# 3-Power-Supply.net
KiCad netlist of a schematic drawn in Altium Designer
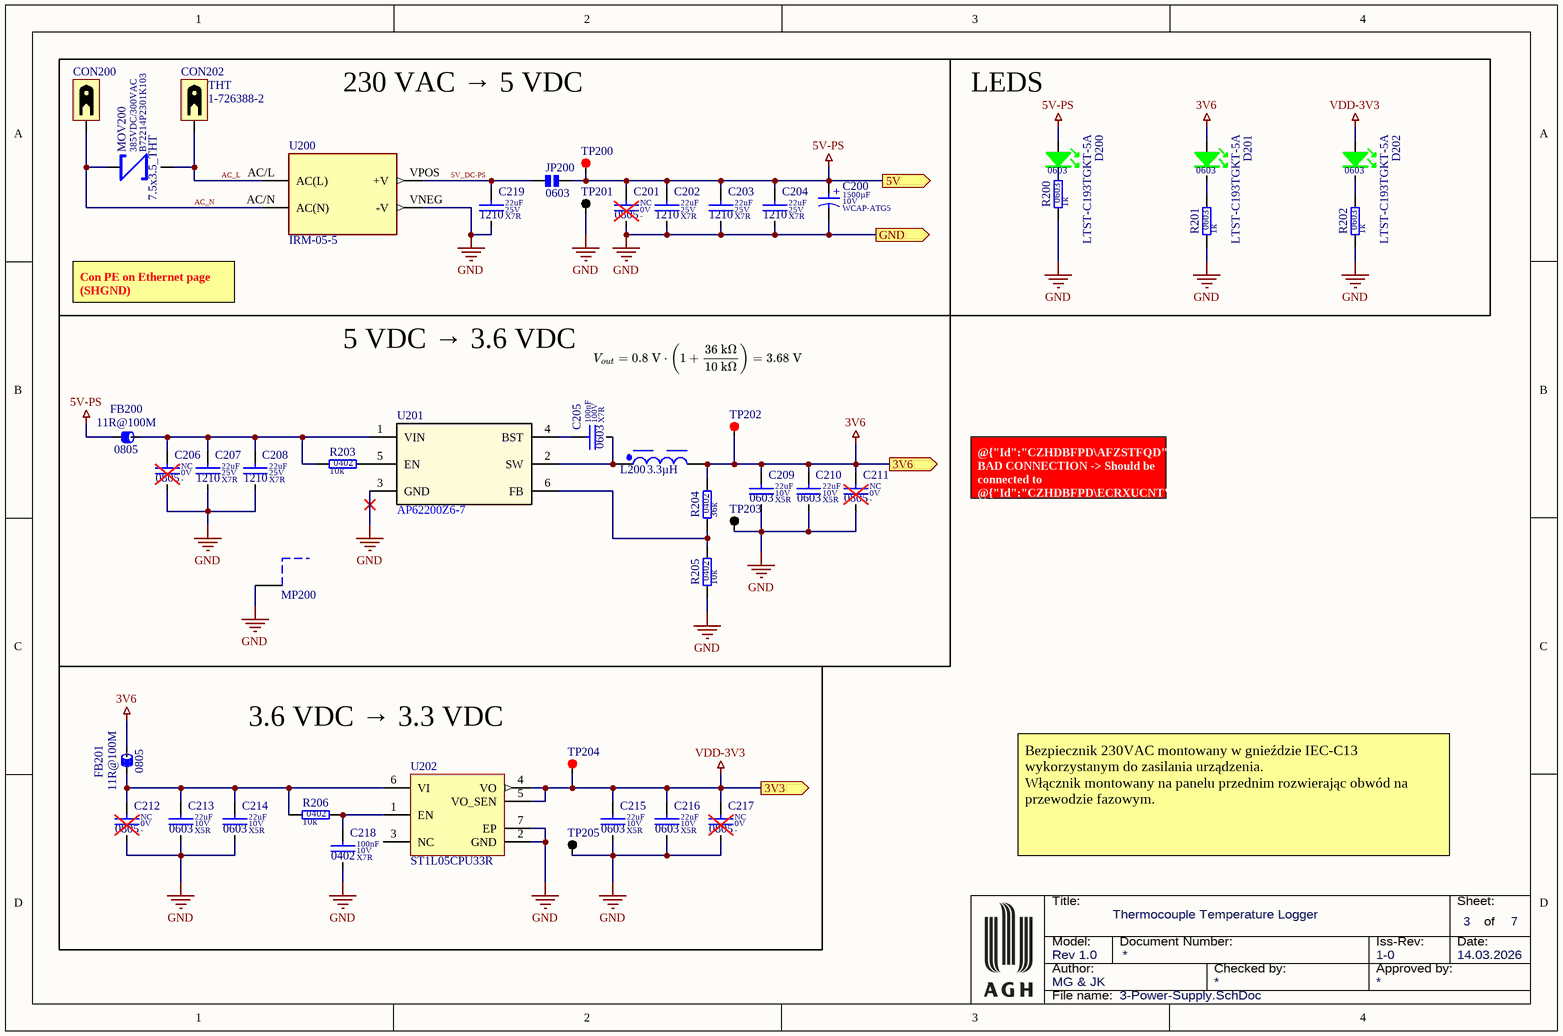
[diagram p0: 3-Power-Supply.SchDoc]

(export (version "E")
  (design (tool "Eeschema 10.0.6"))
  (components
    (comp (ref "C200")
      (value "1500µF")
      (footprint "WCAP-ATG5_D8H20")
      (description "WCAP-ATG5 Aluminum Electrolytic Capacitor, Radial, THT, D8 x H20mm, 1500µF, 10V")
      (fields
        (field (name "MANUFACTURER PART NUMBER") "860020274017")
        (field (name "MATCH CODE") "WCAP-ATG5")
        (field (name "MANUFACTURER") "Wurth Elektronik")
        (field (name "RATED VOLTAGE (DC)") "10V")
      )
      (libsource (lib "Altium_WCAP-ATG5 (rev22d)") (part "860020274017"))
    )
    (comp (ref "C201")
      (value "NC")
      (footprint "C_NC_0805_2012")
      (description "Capacitor")
      (fields
        (field (name "DIELECTRIC") "-")
        (field (name "VOLTAGE") "0V")
        (field (name "SCH_FOOTPRINT") "0805")
        (field (name "PART NUMBER") "C_GENERIC_0805")
      )
      (libsource (lib "Library") (part "C_NC"))
    )
    (comp (ref "C202")
      (value "22uF")
      (footprint "C_1210_3225")
      (description "Capacitor")
      (fields
        (field (name "DIELECTRIC") "X7R")
        (field (name "VOLTAGE") "25V")
        (field (name "SCH_FOOTPRINT") "1210")
        (field (name "PART NUMBER") "C_22uF_25V_X7R_1210_20")
        (field (name "MANUFACTURER") "Murata")
      )
      (libsource (lib "Library") (part "C"))
    )
    (comp (ref "C203")
      (value "22uF")
      (footprint "C_1210_3225")
      (description "Capacitor")
      (fields
        (field (name "DIELECTRIC") "X7R")
        (field (name "VOLTAGE") "25V")
        (field (name "SCH_FOOTPRINT") "1210")
        (field (name "PART NUMBER") "C_22uF_25V_X7R_1210_20")
        (field (name "MANUFACTURER") "Murata")
      )
      (libsource (lib "Library") (part "C"))
    )
    (comp (ref "C204")
      (value "22uF")
      (footprint "C_1210_3225")
      (description "Capacitor")
      (fields
        (field (name "DIELECTRIC") "X7R")
        (field (name "VOLTAGE") "25V")
        (field (name "SCH_FOOTPRINT") "1210")
        (field (name "PART NUMBER") "C_22uF_25V_X7R_1210_20")
        (field (name "MANUFACTURER") "Murata")
      )
      (libsource (lib "Library") (part "C"))
    )
    (comp (ref "C205")
      (value "100nF")
      (footprint "C_0603_1608")
      (description "Capacitor")
      (fields
        (field (name "DIELECTRIC") "X7R")
        (field (name "VOLTAGE") "100V")
        (field (name "SCH_FOOTPRINT") "0603")
        (field (name "PART NUMBER") "C_100nF_100V_X7R_0603_10")
        (field (name "MANUFACTURER") "Kemet")
      )
      (libsource (lib "Library") (part "C"))
    )
    (comp (ref "C206")
      (value "NC")
      (footprint "C_NC_0805_2012")
      (description "Capacitor")
      (fields
        (field (name "DIELECTRIC") "-")
        (field (name "VOLTAGE") "0V")
        (field (name "SCH_FOOTPRINT") "0805")
        (field (name "PART NUMBER") "C_GENERIC_0805")
      )
      (libsource (lib "Library") (part "C_NC"))
    )
    (comp (ref "C207")
      (value "22uF")
      (footprint "C_1210_3225")
      (description "Capacitor")
      (fields
        (field (name "DIELECTRIC") "X7R")
        (field (name "VOLTAGE") "25V")
        (field (name "SCH_FOOTPRINT") "1210")
        (field (name "PART NUMBER") "C_22uF_25V_X7R_1210_20")
        (field (name "MANUFACTURER") "Murata")
      )
      (libsource (lib "Library") (part "C"))
    )
    (comp (ref "C208")
      (value "22uF")
      (footprint "C_1210_3225")
      (description "Capacitor")
      (fields
        (field (name "DIELECTRIC") "X7R")
        (field (name "VOLTAGE") "25V")
        (field (name "SCH_FOOTPRINT") "1210")
        (field (name "PART NUMBER") "C_22uF_25V_X7R_1210_20")
        (field (name "MANUFACTURER") "Murata")
      )
      (libsource (lib "Library") (part "C"))
    )
    (comp (ref "C209")
      (value "22uF")
      (footprint "C_0603_1608")
      (description "Capacitor")
      (fields
        (field (name "DIELECTRIC") "X5R")
        (field (name "VOLTAGE") "10V")
        (field (name "SCH_FOOTPRINT") "0603")
        (field (name "PART NUMBER") "C_22uF_10V_X5R_0603_20")
        (field (name "MANUFACTURER") "Murata")
      )
      (libsource (lib "Library") (part "C"))
    )
    (comp (ref "C210")
      (value "22uF")
      (footprint "C_0603_1608")
      (description "Capacitor")
      (fields
        (field (name "DIELECTRIC") "X5R")
        (field (name "VOLTAGE") "10V")
        (field (name "SCH_FOOTPRINT") "0603")
        (field (name "PART NUMBER") "C_22uF_10V_X5R_0603_20")
        (field (name "MANUFACTURER") "Murata")
      )
      (libsource (lib "Library") (part "C"))
    )
    (comp (ref "C211")
      (value "NC")
      (footprint "C_NC_0805_2012")
      (description "Capacitor")
      (fields
        (field (name "DIELECTRIC") "-")
        (field (name "VOLTAGE") "0V")
        (field (name "SCH_FOOTPRINT") "0805")
        (field (name "PART NUMBER") "C_GENERIC_0805")
      )
      (libsource (lib "Library") (part "C_NC"))
    )
    (comp (ref "C212")
      (value "NC")
      (footprint "C_NC_0805_2012")
      (description "Capacitor")
      (fields
        (field (name "DIELECTRIC") "-")
        (field (name "VOLTAGE") "0V")
        (field (name "SCH_FOOTPRINT") "0805")
        (field (name "PART NUMBER") "C_GENERIC_0805")
      )
      (libsource (lib "Library") (part "C_NC"))
    )
    (comp (ref "C213")
      (value "22uF")
      (footprint "C_0603_1608")
      (description "Capacitor")
      (fields
        (field (name "DIELECTRIC") "X5R")
        (field (name "VOLTAGE") "10V")
        (field (name "SCH_FOOTPRINT") "0603")
        (field (name "PART NUMBER") "C_22uF_10V_X5R_0603_20")
        (field (name "MANUFACTURER") "Murata")
      )
      (libsource (lib "Library") (part "C"))
    )
    (comp (ref "C214")
      (value "22uF")
      (footprint "C_0603_1608")
      (description "Capacitor")
      (fields
        (field (name "DIELECTRIC") "X5R")
        (field (name "VOLTAGE") "10V")
        (field (name "SCH_FOOTPRINT") "0603")
        (field (name "PART NUMBER") "C_22uF_10V_X5R_0603_20")
        (field (name "MANUFACTURER") "Murata")
      )
      (libsource (lib "Library") (part "C"))
    )
    (comp (ref "C215")
      (value "22uF")
      (footprint "C_0603_1608")
      (description "Capacitor")
      (fields
        (field (name "DIELECTRIC") "X5R")
        (field (name "VOLTAGE") "10V")
        (field (name "SCH_FOOTPRINT") "0603")
        (field (name "PART NUMBER") "C_22uF_10V_X5R_0603_20")
        (field (name "MANUFACTURER") "Murata")
      )
      (libsource (lib "Library") (part "C"))
    )
    (comp (ref "C216")
      (value "22uF")
      (footprint "C_0603_1608")
      (description "Capacitor")
      (fields
        (field (name "DIELECTRIC") "X5R")
        (field (name "VOLTAGE") "10V")
        (field (name "SCH_FOOTPRINT") "0603")
        (field (name "PART NUMBER") "C_22uF_10V_X5R_0603_20")
        (field (name "MANUFACTURER") "Murata")
      )
      (libsource (lib "Library") (part "C"))
    )
    (comp (ref "C217")
      (value "NC")
      (footprint "C_NC_0805_2012")
      (description "Capacitor")
      (fields
        (field (name "DIELECTRIC") "-")
        (field (name "VOLTAGE") "0V")
        (field (name "SCH_FOOTPRINT") "0805")
        (field (name "PART NUMBER") "C_GENERIC_0805")
      )
      (libsource (lib "Library") (part "C_NC"))
    )
    (comp (ref "C218")
      (value "100nF")
      (footprint "C_0402_1005")
      (description "Capacitor")
      (fields
        (field (name "DIELECTRIC") "X7R")
        (field (name "VOLTAGE") "10V")
        (field (name "SCH_FOOTPRINT") "0402")
        (field (name "PART NUMBER") "C_100nF_10V_X7R_0402_10")
        (field (name "MANUFACTURER") "Murata")
      )
      (libsource (lib "Library") (part "C"))
    )
    (comp (ref "C219")
      (value "22uF")
      (footprint "C_1210_3225")
      (description "Capacitor")
      (fields
        (field (name "DIELECTRIC") "X7R")
        (field (name "VOLTAGE") "25V")
        (field (name "SCH_FOOTPRINT") "1210")
        (field (name "PART NUMBER") "C_22uF_25V_X7R_1210_20")
        (field (name "MANUFACTURER") "Murata")
      )
      (libsource (lib "Library") (part "C"))
    )
    (comp (ref "CON200")
      (value "Terminal for PE")
      (footprint "TP_1-726388-2")
      (description "Terminal")
      (fields
        (field (name "PART NUMBER") "TP_TERMINAL_1-726388-2")
        (field (name "MANUFACTURER") "TE Connectivity")
      )
      (libsource (lib "Library") (part "TP_TERMINAL"))
    )
    (comp (ref "CON202")
      (value "1-726388-2")
      (footprint "TP_1-726388-2")
      (description "Terminal")
      (fields
        (field (name "SCH_FOOTPRINT") "THT")
        (field (name "PART NUMBER") "TP_TERMINAL_1-726388-2")
        (field (name "MANUFACTURER") "TE Connectivity")
      )
      (libsource (lib "Library") (part "TP_TERMINAL"))
    )
    (comp (ref "D200")
      (value "LTST-C193TGKT-5A")
      (footprint "OL_0603_1608")
      (description "LED GREEN")
      (fields
        (field (name "SCH_FOOTPRINT") "0603")
        (field (name "PART NUMBER") "OL_G_0603_LTST-C193TGKT-5A")
        (field (name "MANUFACTURER") "Lite-On")
      )
      (libsource (lib "Library") (part "OL_G"))
    )
    (comp (ref "D201")
      (value "LTST-C193TGKT-5A")
      (footprint "OL_0603_1608")
      (description "LED GREEN")
      (fields
        (field (name "SCH_FOOTPRINT") "0603")
        (field (name "PART NUMBER") "OL_G_0603_LTST-C193TGKT-5A")
        (field (name "MANUFACTURER") "Lite-On")
      )
      (libsource (lib "Library") (part "OL_G"))
    )
    (comp (ref "D202")
      (value "LTST-C193TGKT-5A")
      (footprint "OL_0603_1608")
      (description "LED GREEN")
      (fields
        (field (name "SCH_FOOTPRINT") "0603")
        (field (name "PART NUMBER") "OL_G_0603_LTST-C193TGKT-5A")
        (field (name "MANUFACTURER") "Lite-On")
      )
      (libsource (lib "Library") (part "OL_G"))
    )
    (comp (ref "FB200")
      (value "11R@100M")
      (footprint "FB_0805_2012")
      (description "Ferrite Bead")
      (fields
        (field (name "SCH_FOOTPRINT") "0805")
        (field (name "PART NUMBER") "FB_2508051107Y0")
        (field (name "MANUFACTURER") "Fair-Rite")
      )
      (libsource (lib "Library") (part "FB"))
    )
    (comp (ref "FB201")
      (value "11R@100M")
      (footprint "FB_0805_2012")
      (description "Ferrite Bead")
      (fields
        (field (name "SCH_FOOTPRINT") "0805")
        (field (name "PART NUMBER") "FB_2508051107Y0")
        (field (name "MANUFACTURER") "Fair-Rite")
      )
      (libsource (lib "") (part "FB_1"))
    )
    (comp (ref "JP200")
      (value "Solder Jumper 0603/1608")
      (footprint "JP_0603_1608")
      (fields (field (name "SCH_FOOTPRINT") "0603") (field (name "PART NUMBER") "JP_0603_1608"))
      (libsource (lib "Library") (part "JP"))
    )
    (comp (ref "L200")
      (value "3.3µH, 2.1A")
      (footprint "WE-SPC_4828")
      (description "WE-SPC SMT Power Inductor, size 4828, 3.3µH, 2.1A, 0.057Ω")
      (fields
        (field (name "MANUFACTURER PART NUMBER") "74408942033")
        (field (name "MANUFACTURER") "Wurth Elektronik")
        (field (name "INDUCTANCE") "3.3µH")
      )
      (libsource (lib "WE-SPC (rev22d)") (part "74408942033"))
    )
    (comp (ref "MOV200")
      (value "B72214P2301K103")
      (footprint "MOV_AXIAL_7.5_3.5")
      (description "Varistor")
      (fields
        (field (name "SCH_FOOTPRINT") "7.5x3.5_THT")
        (field (name "VOLTAGE") "385VDC/300VAC")
        (field (name "PART NUMBER") "MOV_385VDC_300VAC_THT")
        (field (name "MANUFACTURER") "Epcos")
      )
      (libsource (lib "Library") (part "MOV"))
    )
    (comp (ref "MP200")
      (value "36702638")
      (footprint "36702638")
      (description "WE-SHC Shielding Cabinet, SMT Frame Seamless, Tin Plated, Tray, 26.3x19.8x8.1mm")
      (fields (field (name "MANUFACTURER") "Wurth Elektronik"))
      (libsource (lib "WE-SHC (rev24a)") (part "36702638"))
    )
    (comp (ref "R200")
      (value "1k")
      (footprint "R_0603_1608")
      (fields
        (field (name "SCH_FOOTPRINT") "0603")
        (field (name "PART NUMBER") "R_1k_0603_1_AECQ0")
        (field (name "VOLTAGE") "75V")
        (field (name "POWER") "100mW")
      )
      (libsource (lib "Library") (part "R"))
    )
    (comp (ref "R201")
      (value "1k")
      (footprint "R_0603_1608")
      (fields
        (field (name "SCH_FOOTPRINT") "0603")
        (field (name "PART NUMBER") "R_1k_0603_1_AECQ0")
        (field (name "VOLTAGE") "75V")
        (field (name "POWER") "100mW")
      )
      (libsource (lib "Library") (part "R"))
    )
    (comp (ref "R202")
      (value "1k")
      (footprint "R_0603_1608")
      (fields
        (field (name "SCH_FOOTPRINT") "0603")
        (field (name "PART NUMBER") "R_1k_0603_1_AECQ0")
        (field (name "VOLTAGE") "75V")
        (field (name "POWER") "100mW")
      )
      (libsource (lib "Library") (part "R"))
    )
    (comp (ref "R203")
      (value "10k")
      (footprint "R_0402_1005")
      (fields
        (field (name "SCH_FOOTPRINT") "0402")
        (field (name "PART NUMBER") "R_10k_0402_1")
        (field (name "VOLTAGE") "50V")
        (field (name "POWER") "63mW")
      )
      (libsource (lib "Library") (part "R"))
    )
    (comp (ref "R204")
      (value "36k")
      (footprint "R_0402_1005")
      (fields
        (field (name "SCH_FOOTPRINT") "0402")
        (field (name "PART NUMBER") "R_36k_0402_1_AECQ0")
        (field (name "VOLTAGE") "50V")
        (field (name "POWER") "100mW")
      )
      (libsource (lib "Library") (part "R"))
    )
    (comp (ref "R205")
      (value "10k")
      (footprint "R_0402_1005")
      (fields
        (field (name "SCH_FOOTPRINT") "0402")
        (field (name "PART NUMBER") "R_10k_0402_1")
        (field (name "VOLTAGE") "50V")
        (field (name "POWER") "63mW")
      )
      (libsource (lib "Library") (part "R"))
    )
    (comp (ref "R206")
      (value "10k")
      (footprint "R_0402_1005")
      (fields
        (field (name "SCH_FOOTPRINT") "0402")
        (field (name "PART NUMBER") "R_10k_0402_1")
        (field (name "VOLTAGE") "50V")
        (field (name "POWER") "63mW")
      )
      (libsource (lib "Library") (part "R"))
    )
    (comp (ref "TP200")
      (value "Test loop THT")
      (footprint "TP_KEYSTONE_5000_RED")
      (description "Testpoint")
      (fields (field (name "PART NUMBER") "TP_LOOP_MICRO_RED") (field (name "MANUFACTURER") "Keystone"))
      (libsource (lib "Library") (part "TP_TESTPOINT_RED"))
    )
    (comp (ref "TP201")
      (value "Test loop THT")
      (footprint "TP_KEYSTONE_5001_BLACK")
      (description "Testpoint")
      (fields (field (name "PART NUMBER") "TP_LOOP_MICRO_BLACK") (field (name "MANUFACTURER") "Keystone"))
      (libsource (lib "Library") (part "TP_TESTPOINT_BLACK"))
    )
    (comp (ref "TP202")
      (value "Test loop THT")
      (footprint "TP_KEYSTONE_5000_RED")
      (description "Testpoint")
      (fields (field (name "PART NUMBER") "TP_LOOP_MICRO_RED") (field (name "MANUFACTURER") "Keystone"))
      (libsource (lib "Library") (part "TP_TESTPOINT_RED"))
    )
    (comp (ref "TP203")
      (value "Test loop THT")
      (footprint "TP_KEYSTONE_5001_BLACK")
      (description "Testpoint")
      (fields (field (name "PART NUMBER") "TP_LOOP_MICRO_BLACK") (field (name "MANUFACTURER") "Keystone"))
      (libsource (lib "Library") (part "TP_TESTPOINT_BLACK"))
    )
    (comp (ref "TP204")
      (value "Test loop THT")
      (footprint "TP_KEYSTONE_5000_RED")
      (description "Testpoint")
      (fields (field (name "PART NUMBER") "TP_LOOP_MICRO_RED") (field (name "MANUFACTURER") "Keystone"))
      (libsource (lib "Library") (part "TP_TESTPOINT_RED"))
    )
    (comp (ref "TP205")
      (value "Test loop THT")
      (footprint "TP_KEYSTONE_5001_BLACK")
      (description "Testpoint")
      (fields (field (name "PART NUMBER") "TP_LOOP_MICRO_BLACK") (field (name "MANUFACTURER") "Keystone"))
      (libsource (lib "Library") (part "TP_TESTPOINT_BLACK"))
    )
    (comp (ref "U200")
      (value "IRM-05-5")
      (footprint "CONV_IRM-05-5")
      (description "Enclosed AC DC Converters 1 Uitgang 5V 1A 85 ~ 305 VAC, 120 ~ 430 VDC Input")
      (fields (field (name "MF") "MEAN WELL"))
      (libsource (lib "IRM-05-5") (part "IRM-05-5"))
    )
    (comp (ref "U201")
      (value "AP62200Z6-7")
      (footprint "SOT563-Z6_1_DIO")
      (description "Description")
      (fields (field (name "COPYRIGHT") "Copyright (C) 2025 Ultra Librarian. All rights reserved."))
      (libsource (lib "AP62200Z6-7") (part "AP62200Z6-7"))
    )
    (comp (ref "U202")
      (value "ST1L05CPU33R")
      (footprint "DFN6D_N")
      (description "Very Low Quiescent BiCMOS Voltage Regulator, 3.3V, 6-Pin VFDFPN, Tape and Reel")
      (libsource (lib "Altium Content Vault") (part "PM-REG-ST1L05C-SQ7"))
    )
  )
  (nets
    (net (code "1") (name "/5V_DC-PS") (class "Default")
      (node (ref "C219") (pin "1") (pinfunction "1_1") (pintype "passive"))
      (node (ref "JP200") (pin "1") (pinfunction "1_1") (pintype "passive"))
      (node (ref "U200") (pin "VPOS") (pinfunction "+V_VPOS") (pintype "output"))
    )
    (net (code "2") (name "/AC_L") (class "Default")
      (node (ref "CON202") (pin "1") (pinfunction "TP_1") (pintype "passive"))
      (node (ref "MOV200") (pin "1") (pintype "passive"))
      (node (ref "U200") (pin "AC/L") (pinfunction "AC(L)_AC/L") (pintype "passive"))
    )
    (net (code "3") (name "/AC_N") (class "Default")
      (node (ref "CON200") (pin "1") (pinfunction "TP_1") (pintype "passive"))
      (node (ref "MOV200") (pin "2") (pintype "passive"))
      (node (ref "U200") (pin "AC/N") (pinfunction "AC(N)_AC/N") (pintype "passive"))
    )
    (net (code "4") (name "3V6") (class "Default")
      (node (ref "C209") (pin "1") (pinfunction "1_1") (pintype "passive"))
      (node (ref "C210") (pin "1") (pinfunction "1_1") (pintype "passive"))
      (node (ref "C211") (pin "1") (pinfunction "1_1") (pintype "passive"))
      (node (ref "D201") (pin "2") (pinfunction "A_2") (pintype "passive"))
      (node (ref "FB201") (pin "2") (pintype "passive"))
      (node (ref "L200") (pin "2") (pinfunction "2_2") (pintype "passive"))
      (node (ref "R204") (pin "2") (pinfunction "2_2") (pintype "passive"))
      (node (ref "TP202") (pin "1") (pinfunction "TP_1") (pintype "passive"))
    )
    (net (code "5") (name "5V-PS") (class "Default")
      (node (ref "C200") (pin "1") (pinfunction "P_1") (pintype "passive"))
      (node (ref "C201") (pin "1") (pinfunction "1_1") (pintype "passive"))
      (node (ref "C202") (pin "1") (pinfunction "1_1") (pintype "passive"))
      (node (ref "C203") (pin "1") (pinfunction "1_1") (pintype "passive"))
      (node (ref "C204") (pin "1") (pinfunction "1_1") (pintype "passive"))
      (node (ref "D200") (pin "2") (pinfunction "A_2") (pintype "passive"))
      (node (ref "FB200") (pin "1") (pintype "passive"))
      (node (ref "JP200") (pin "2") (pinfunction "2_2") (pintype "passive"))
      (node (ref "TP200") (pin "1") (pinfunction "TP_1") (pintype "passive"))
    )
    (net (code "6") (name "GND") (class "Default")
      (node (ref "C200") (pin "2") (pinfunction "N_2") (pintype "passive"))
      (node (ref "C201") (pin "2") (pinfunction "2_2") (pintype "passive"))
      (node (ref "C202") (pin "2") (pinfunction "2_2") (pintype "passive"))
      (node (ref "C203") (pin "2") (pinfunction "2_2") (pintype "passive"))
      (node (ref "C204") (pin "2") (pinfunction "2_2") (pintype "passive"))
      (node (ref "C206") (pin "2") (pinfunction "2_2") (pintype "passive"))
      (node (ref "C207") (pin "2") (pinfunction "2_2") (pintype "passive"))
      (node (ref "C208") (pin "2") (pinfunction "2_2") (pintype "passive"))
      (node (ref "C209") (pin "2") (pinfunction "2_2") (pintype "passive"))
      (node (ref "C210") (pin "2") (pinfunction "2_2") (pintype "passive"))
      (node (ref "C211") (pin "2") (pinfunction "2_2") (pintype "passive"))
      (node (ref "C212") (pin "2") (pinfunction "2_2") (pintype "passive"))
      (node (ref "C213") (pin "2") (pinfunction "2_2") (pintype "passive"))
      (node (ref "C214") (pin "2") (pinfunction "2_2") (pintype "passive"))
      (node (ref "C215") (pin "2") (pinfunction "2_2") (pintype "passive"))
      (node (ref "C216") (pin "2") (pinfunction "2_2") (pintype "passive"))
      (node (ref "C217") (pin "2") (pinfunction "2_2") (pintype "passive"))
      (node (ref "C218") (pin "2") (pinfunction "2_2") (pintype "passive"))
      (node (ref "C219") (pin "2") (pinfunction "2_2") (pintype "passive"))
      (node (ref "MP200") (pin "1") (pinfunction "1_1") (pintype "passive"))
      (node (ref "R200") (pin "1") (pinfunction "1_1") (pintype "passive"))
      (node (ref "R201") (pin "1") (pinfunction "1_1") (pintype "passive"))
      (node (ref "R202") (pin "1") (pinfunction "1_1") (pintype "passive"))
      (node (ref "R205") (pin "1") (pinfunction "1_1") (pintype "passive"))
      (node (ref "TP201") (pin "1") (pinfunction "TP_1") (pintype "passive"))
      (node (ref "TP203") (pin "1") (pinfunction "TP_1") (pintype "passive"))
      (node (ref "TP205") (pin "1") (pinfunction "TP_1") (pintype "passive"))
      (node (ref "U200") (pin "VNEG") (pinfunction "-V_VNEG") (pintype "output"))
      (node (ref "U201") (pin "3") (pinfunction "GND_3") (pintype "passive"))
      (node (ref "U202") (pin "2") (pinfunction "GND_2") (pintype "passive"))
      (node (ref "U202") (pin "7") (pinfunction "EP_7") (pintype "passive"))
    )
    (net (code "7") (name "Net-(D200-K)") (class "Default")
      (node (ref "D200") (pin "1") (pinfunction "K_1") (pintype "passive"))
      (node (ref "R200") (pin "2") (pinfunction "2_2") (pintype "passive"))
    )
    (net (code "8") (name "Net-(D201-K)") (class "Default")
      (node (ref "D201") (pin "1") (pinfunction "K_1") (pintype "passive"))
      (node (ref "R201") (pin "2") (pinfunction "2_2") (pintype "passive"))
    )
    (net (code "9") (name "Net-(D202-K)") (class "Default")
      (node (ref "D202") (pin "1") (pinfunction "K_1") (pintype "passive"))
      (node (ref "R202") (pin "2") (pinfunction "2_2") (pintype "passive"))
    )
    (net (code "10") (name "Net-(U201-BST)") (class "Default")
      (node (ref "C205") (pin "1") (pinfunction "1_1") (pintype "passive"))
      (node (ref "U201") (pin "4") (pinfunction "BST_4") (pintype "passive"))
    )
    (net (code "11") (name "Net-(U201-EN)") (class "Default")
      (node (ref "R203") (pin "2") (pinfunction "2_2") (pintype "passive"))
      (node (ref "U201") (pin "5") (pinfunction "EN_5") (pintype "passive"))
    )
    (net (code "12") (name "Net-(U201-FB)") (class "Default")
      (node (ref "R204") (pin "1") (pinfunction "1_1") (pintype "passive"))
      (node (ref "R205") (pin "2") (pinfunction "2_2") (pintype "passive"))
      (node (ref "U201") (pin "6") (pinfunction "FB_6") (pintype "passive"))
    )
    (net (code "13") (name "Net-(U201-SW)") (class "Default")
      (node (ref "C205") (pin "2") (pinfunction "2_2") (pintype "passive"))
      (node (ref "L200") (pin "1") (pinfunction "1_1") (pintype "passive"))
      (node (ref "U201") (pin "2") (pinfunction "SW_2") (pintype "passive"))
    )
    (net (code "14") (name "Net-(U201-VIN)") (class "Default")
      (node (ref "C206") (pin "1") (pinfunction "1_1") (pintype "passive"))
      (node (ref "C207") (pin "1") (pinfunction "1_1") (pintype "passive"))
      (node (ref "C208") (pin "1") (pinfunction "1_1") (pintype "passive"))
      (node (ref "FB200") (pin "2") (pintype "passive"))
      (node (ref "R203") (pin "1") (pinfunction "1_1") (pintype "passive"))
      (node (ref "U201") (pin "1") (pinfunction "VIN_1") (pintype "power_in"))
    )
    (net (code "15") (name "Net-(U202-EN)") (class "Default")
      (node (ref "C218") (pin "1") (pinfunction "1_1") (pintype "passive"))
      (node (ref "R206") (pin "2") (pinfunction "2_2") (pintype "passive"))
      (node (ref "U202") (pin "1") (pinfunction "EN_1") (pintype "passive"))
    )
    (net (code "16") (name "Net-(U202-VI)") (class "Default")
      (node (ref "C212") (pin "1") (pinfunction "1_1") (pintype "passive"))
      (node (ref "C213") (pin "1") (pinfunction "1_1") (pintype "passive"))
      (node (ref "C214") (pin "1") (pinfunction "1_1") (pintype "passive"))
      (node (ref "FB201") (pin "1") (pintype "passive"))
      (node (ref "R206") (pin "1") (pinfunction "1_1") (pintype "passive"))
      (node (ref "U202") (pin "6") (pinfunction "VI_6") (pintype "power_in"))
    )
    (net (code "17") (name "VDD-3V3") (class "Default")
      (node (ref "C215") (pin "1") (pinfunction "1_1") (pintype "passive"))
      (node (ref "C216") (pin "1") (pinfunction "1_1") (pintype "passive"))
      (node (ref "C217") (pin "1") (pinfunction "1_1") (pintype "passive"))
      (node (ref "D202") (pin "2") (pinfunction "A_2") (pintype "passive"))
      (node (ref "TP204") (pin "1") (pinfunction "TP_1") (pintype "passive"))
      (node (ref "U202") (pin "4") (pinfunction "VO_4") (pintype "output"))
      (node (ref "U202") (pin "5") (pinfunction "VO_SEN_5") (pintype "passive"))
    )
    (net (code "18") (name "unconnected-(U202-NC-Pad3)") (class "Default")
      (node (ref "U202") (pin "3") (pinfunction "NC_3") (pintype "passive"))
    )
  )
)
